# 5V_AC-DC_reg.net
KiCad netlist of a schematic drawn in EAGLE
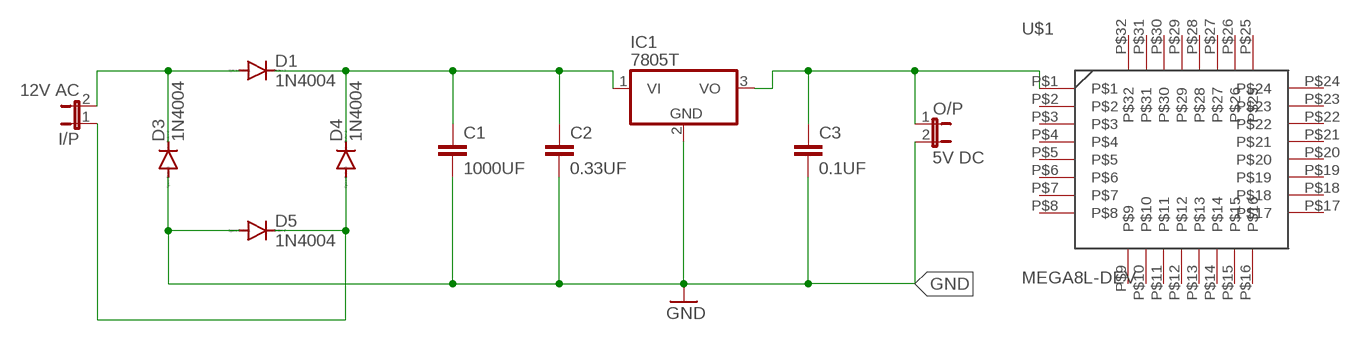
[diagram p0: schematic, sheet 1]

(export (version "E")
  (design (tool "Eeschema 10.0.6"))
  (components
    (comp (ref "C1")
      (value "1000UF")
      (footprint "eagle-import:C2.5-3")
      (libsource (lib "eagle-import") (part "C2,5-3"))
    )
    (comp (ref "C2")
      (value "0.33UF")
      (footprint "eagle-import:C2.5-3")
      (libsource (lib "eagle-import") (part "C2,5-3"))
    )
    (comp (ref "C3")
      (value "0.1UF")
      (footprint "eagle-import:C2.5-3")
      (libsource (lib "eagle-import") (part "C2,5-3"))
    )
    (comp (ref "D1")
      (value "1N4004")
      (footprint "eagle-import:DO41-10")
      (libsource (lib "eagle-import") (part "1N4004"))
    )
    (comp (ref "D3")
      (value "1N4004")
      (footprint "eagle-import:DO41-10")
      (libsource (lib "eagle-import") (part "1N4004"))
    )
    (comp (ref "D4")
      (value "1N4004")
      (footprint "eagle-import:DO41-10")
      (libsource (lib "eagle-import") (part "1N4004"))
    )
    (comp (ref "D5")
      (value "1N4004")
      (footprint "eagle-import:DO41-10")
      (libsource (lib "eagle-import") (part "1N4004"))
    )
    (comp (ref "I/P")
      (value "12V AC")
      (footprint "eagle-import:JP1")
      (libsource (lib "eagle-import") (part "JP1E"))
    )
    (comp (ref "IC1")
      (value "7805T")
      (footprint "eagle-import:TO220H")
      (libsource (lib "eagle-import") (part "78T05"))
    )
    (comp (ref "O/P")
      (value "5V DC")
      (footprint "eagle-import:JP1")
      (libsource (lib "eagle-import") (part "JP1E"))
    )
    (comp (ref "U$1")
      (value "MEGA8L-DEV")
      (footprint "eagle-import:TQFP-MEGA8L")
      (libsource (lib "eagle-import") (part "MEGA8L-DEV"))
    )
  )
  (nets
    (net (code "1") (name "GND") (class "Default")
      (node (ref "C1") (pin "2") (pinfunction "2_2") (pintype "passive"))
      (node (ref "C2") (pin "2") (pinfunction "2_2") (pintype "passive"))
      (node (ref "C3") (pin "2") (pinfunction "2_2") (pintype "passive"))
      (node (ref "D3") (pin "A") (pinfunction "A_A") (pintype "passive"))
      (node (ref "D5") (pin "A") (pinfunction "A_A") (pintype "passive"))
      (node (ref "IC1") (pin "2") (pinfunction "GND_2") (pintype "passive"))
      (node (ref "O/P") (pin "2") (pinfunction "2_2") (pintype "passive"))
    )
    (net (code "2") (name "Net-(D1-PadA)") (class "Default")
      (node (ref "D1") (pin "A") (pinfunction "A_A") (pintype "passive"))
      (node (ref "D3") (pin "C") (pinfunction "C_C") (pintype "passive"))
      (node (ref "I/P") (pin "2") (pinfunction "2_2") (pintype "passive"))
    )
    (net (code "3") (name "Net-(D4-PadA)") (class "Default")
      (node (ref "D4") (pin "A") (pinfunction "A_A") (pintype "passive"))
      (node (ref "D5") (pin "C") (pinfunction "C_C") (pintype "passive"))
      (node (ref "I/P") (pin "1") (pinfunction "1_1") (pintype "passive"))
    )
    (net (code "4") (name "Net-(IC1-VI)") (class "Default")
      (node (ref "C1") (pin "1") (pinfunction "1_1") (pintype "passive"))
      (node (ref "C2") (pin "1") (pinfunction "1_1") (pintype "passive"))
      (node (ref "D1") (pin "C") (pinfunction "C_C") (pintype "passive"))
      (node (ref "D4") (pin "C") (pinfunction "C_C") (pintype "passive"))
      (node (ref "IC1") (pin "1") (pinfunction "VI_1") (pintype "input"))
    )
    (net (code "5") (name "Net-(IC1-VO)") (class "Default")
      (node (ref "C3") (pin "1") (pinfunction "1_1") (pintype "passive"))
      (node (ref "IC1") (pin "3") (pinfunction "VO_3") (pintype "passive"))
      (node (ref "O/P") (pin "1") (pinfunction "1_1") (pintype "passive"))
      (node (ref "U$1") (pin "P$1") (pinfunction "P$1_P$1") (pintype "bidirectional"))
    )
    (net (code "6") (name "unconnected-(U$1-PadP$2)") (class "Default")
      (node (ref "U$1") (pin "P$2") (pinfunction "P$2_P$2") (pintype "bidirectional"))
    )
    (net (code "7") (name "unconnected-(U$1-PadP$3)") (class "Default")
      (node (ref "U$1") (pin "P$3") (pinfunction "P$3_P$3") (pintype "bidirectional"))
    )
    (net (code "8") (name "unconnected-(U$1-PadP$4)") (class "Default")
      (node (ref "U$1") (pin "P$4") (pinfunction "P$4_P$4") (pintype "bidirectional"))
    )
    (net (code "9") (name "unconnected-(U$1-PadP$5)") (class "Default")
      (node (ref "U$1") (pin "P$5") (pinfunction "P$5_P$5") (pintype "bidirectional"))
    )
    (net (code "10") (name "unconnected-(U$1-PadP$6)") (class "Default")
      (node (ref "U$1") (pin "P$6") (pinfunction "P$6_P$6") (pintype "bidirectional"))
    )
    (net (code "11") (name "unconnected-(U$1-PadP$7)") (class "Default")
      (node (ref "U$1") (pin "P$7") (pinfunction "P$7_P$7") (pintype "bidirectional"))
    )
    (net (code "12") (name "unconnected-(U$1-PadP$8)") (class "Default")
      (node (ref "U$1") (pin "P$8") (pinfunction "P$8_P$8") (pintype "bidirectional"))
    )
    (net (code "13") (name "unconnected-(U$1-PadP$9)") (class "Default")
      (node (ref "U$1") (pin "P$9") (pinfunction "P$9_P$9") (pintype "bidirectional"))
    )
    (net (code "14") (name "unconnected-(U$1-PadP$10)") (class "Default")
      (node (ref "U$1") (pin "P$10") (pinfunction "P$10_P$10") (pintype "bidirectional"))
    )
    (net (code "15") (name "unconnected-(U$1-PadP$11)") (class "Default")
      (node (ref "U$1") (pin "P$11") (pinfunction "P$11_P$11") (pintype "bidirectional"))
    )
    (net (code "16") (name "unconnected-(U$1-PadP$12)") (class "Default")
      (node (ref "U$1") (pin "P$12") (pinfunction "P$12_P$12") (pintype "bidirectional"))
    )
    (net (code "17") (name "unconnected-(U$1-PadP$13)") (class "Default")
      (node (ref "U$1") (pin "P$13") (pinfunction "P$13_P$13") (pintype "bidirectional"))
    )
    (net (code "18") (name "unconnected-(U$1-PadP$14)") (class "Default")
      (node (ref "U$1") (pin "P$14") (pinfunction "P$14_P$14") (pintype "bidirectional"))
    )
    (net (code "19") (name "unconnected-(U$1-PadP$15)") (class "Default")
      (node (ref "U$1") (pin "P$15") (pinfunction "P$15_P$15") (pintype "bidirectional"))
    )
    (net (code "20") (name "unconnected-(U$1-PadP$16)") (class "Default")
      (node (ref "U$1") (pin "P$16") (pinfunction "P$16_P$16") (pintype "bidirectional"))
    )
    (net (code "21") (name "unconnected-(U$1-PadP$17)") (class "Default")
      (node (ref "U$1") (pin "P$17") (pinfunction "P$17_P$17") (pintype "bidirectional"))
    )
    (net (code "22") (name "unconnected-(U$1-PadP$18)") (class "Default")
      (node (ref "U$1") (pin "P$18") (pinfunction "P$18_P$18") (pintype "bidirectional"))
    )
    (net (code "23") (name "unconnected-(U$1-PadP$19)") (class "Default")
      (node (ref "U$1") (pin "P$19") (pinfunction "P$19_P$19") (pintype "bidirectional"))
    )
    (net (code "24") (name "unconnected-(U$1-PadP$20)") (class "Default")
      (node (ref "U$1") (pin "P$20") (pinfunction "P$20_P$20") (pintype "bidirectional"))
    )
    (net (code "25") (name "unconnected-(U$1-PadP$21)") (class "Default")
      (node (ref "U$1") (pin "P$21") (pinfunction "P$21_P$21") (pintype "bidirectional"))
    )
    (net (code "26") (name "unconnected-(U$1-PadP$22)") (class "Default")
      (node (ref "U$1") (pin "P$22") (pinfunction "P$22_P$22") (pintype "bidirectional"))
    )
    (net (code "27") (name "unconnected-(U$1-PadP$23)") (class "Default")
      (node (ref "U$1") (pin "P$23") (pinfunction "P$23_P$23") (pintype "bidirectional"))
    )
    (net (code "28") (name "unconnected-(U$1-PadP$24)") (class "Default")
      (node (ref "U$1") (pin "P$24") (pinfunction "P$24_P$24") (pintype "bidirectional"))
    )
    (net (code "29") (name "unconnected-(U$1-PadP$25)") (class "Default")
      (node (ref "U$1") (pin "P$25") (pinfunction "P$25_P$25") (pintype "bidirectional"))
    )
    (net (code "30") (name "unconnected-(U$1-PadP$26)") (class "Default")
      (node (ref "U$1") (pin "P$26") (pinfunction "P$26_P$26") (pintype "bidirectional"))
    )
    (net (code "31") (name "unconnected-(U$1-PadP$27)") (class "Default")
      (node (ref "U$1") (pin "P$27") (pinfunction "P$27_P$27") (pintype "bidirectional"))
    )
    (net (code "32") (name "unconnected-(U$1-PadP$28)") (class "Default")
      (node (ref "U$1") (pin "P$28") (pinfunction "P$28_P$28") (pintype "bidirectional"))
    )
    (net (code "33") (name "unconnected-(U$1-PadP$29)") (class "Default")
      (node (ref "U$1") (pin "P$29") (pinfunction "P$29_P$29") (pintype "bidirectional"))
    )
    (net (code "34") (name "unconnected-(U$1-PadP$30)") (class "Default")
      (node (ref "U$1") (pin "P$30") (pinfunction "P$30_P$30") (pintype "bidirectional"))
    )
    (net (code "35") (name "unconnected-(U$1-PadP$31)") (class "Default")
      (node (ref "U$1") (pin "P$31") (pinfunction "P$31_P$31") (pintype "bidirectional"))
    )
    (net (code "36") (name "unconnected-(U$1-PadP$32)") (class "Default")
      (node (ref "U$1") (pin "P$32") (pinfunction "P$32_P$32") (pintype "bidirectional"))
    )
  )
)
